# CanBus.net
KiCad netlist of a schematic drawn in EAGLE
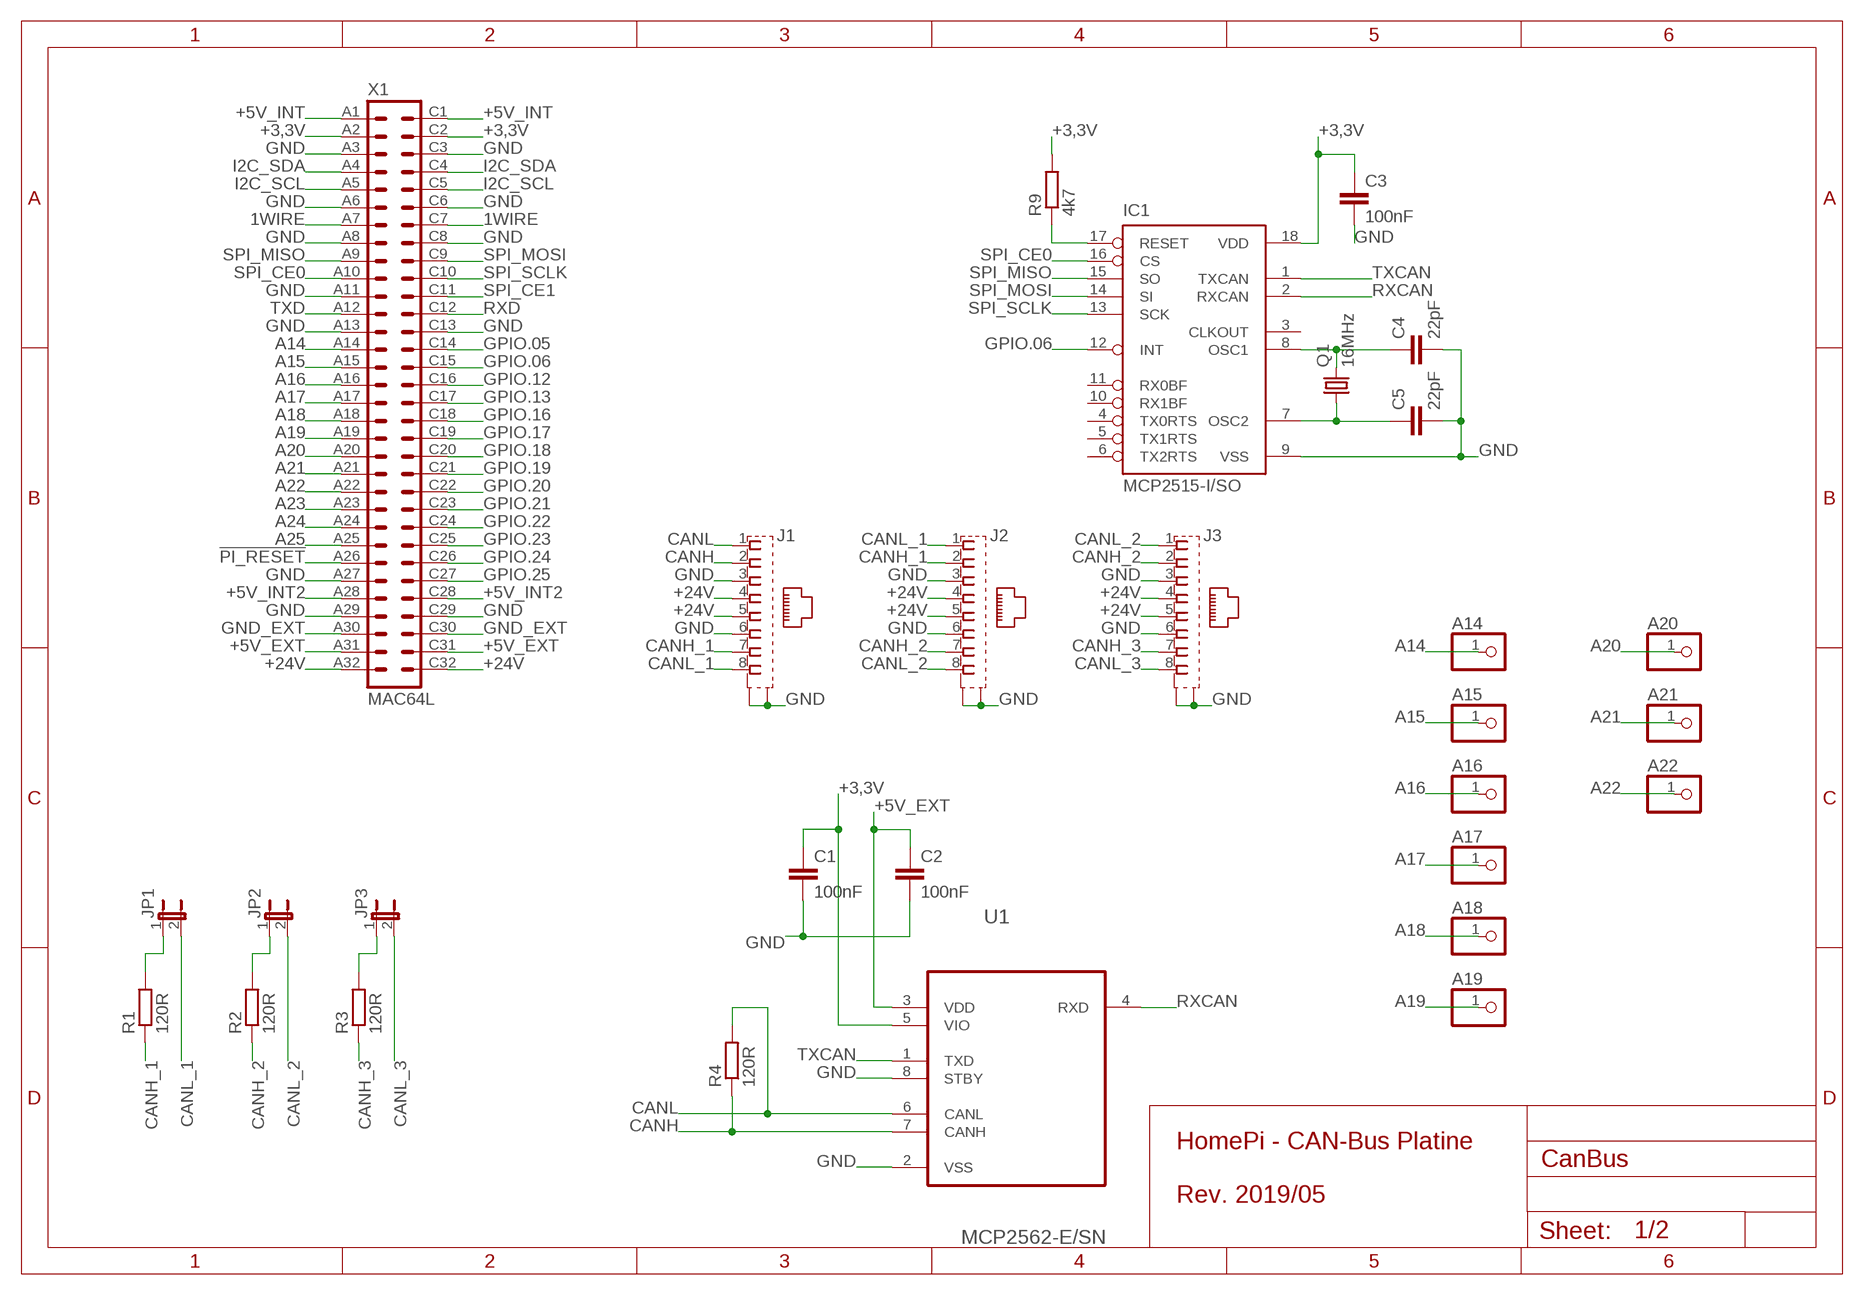
[diagram p0: schematic, sheet 1]
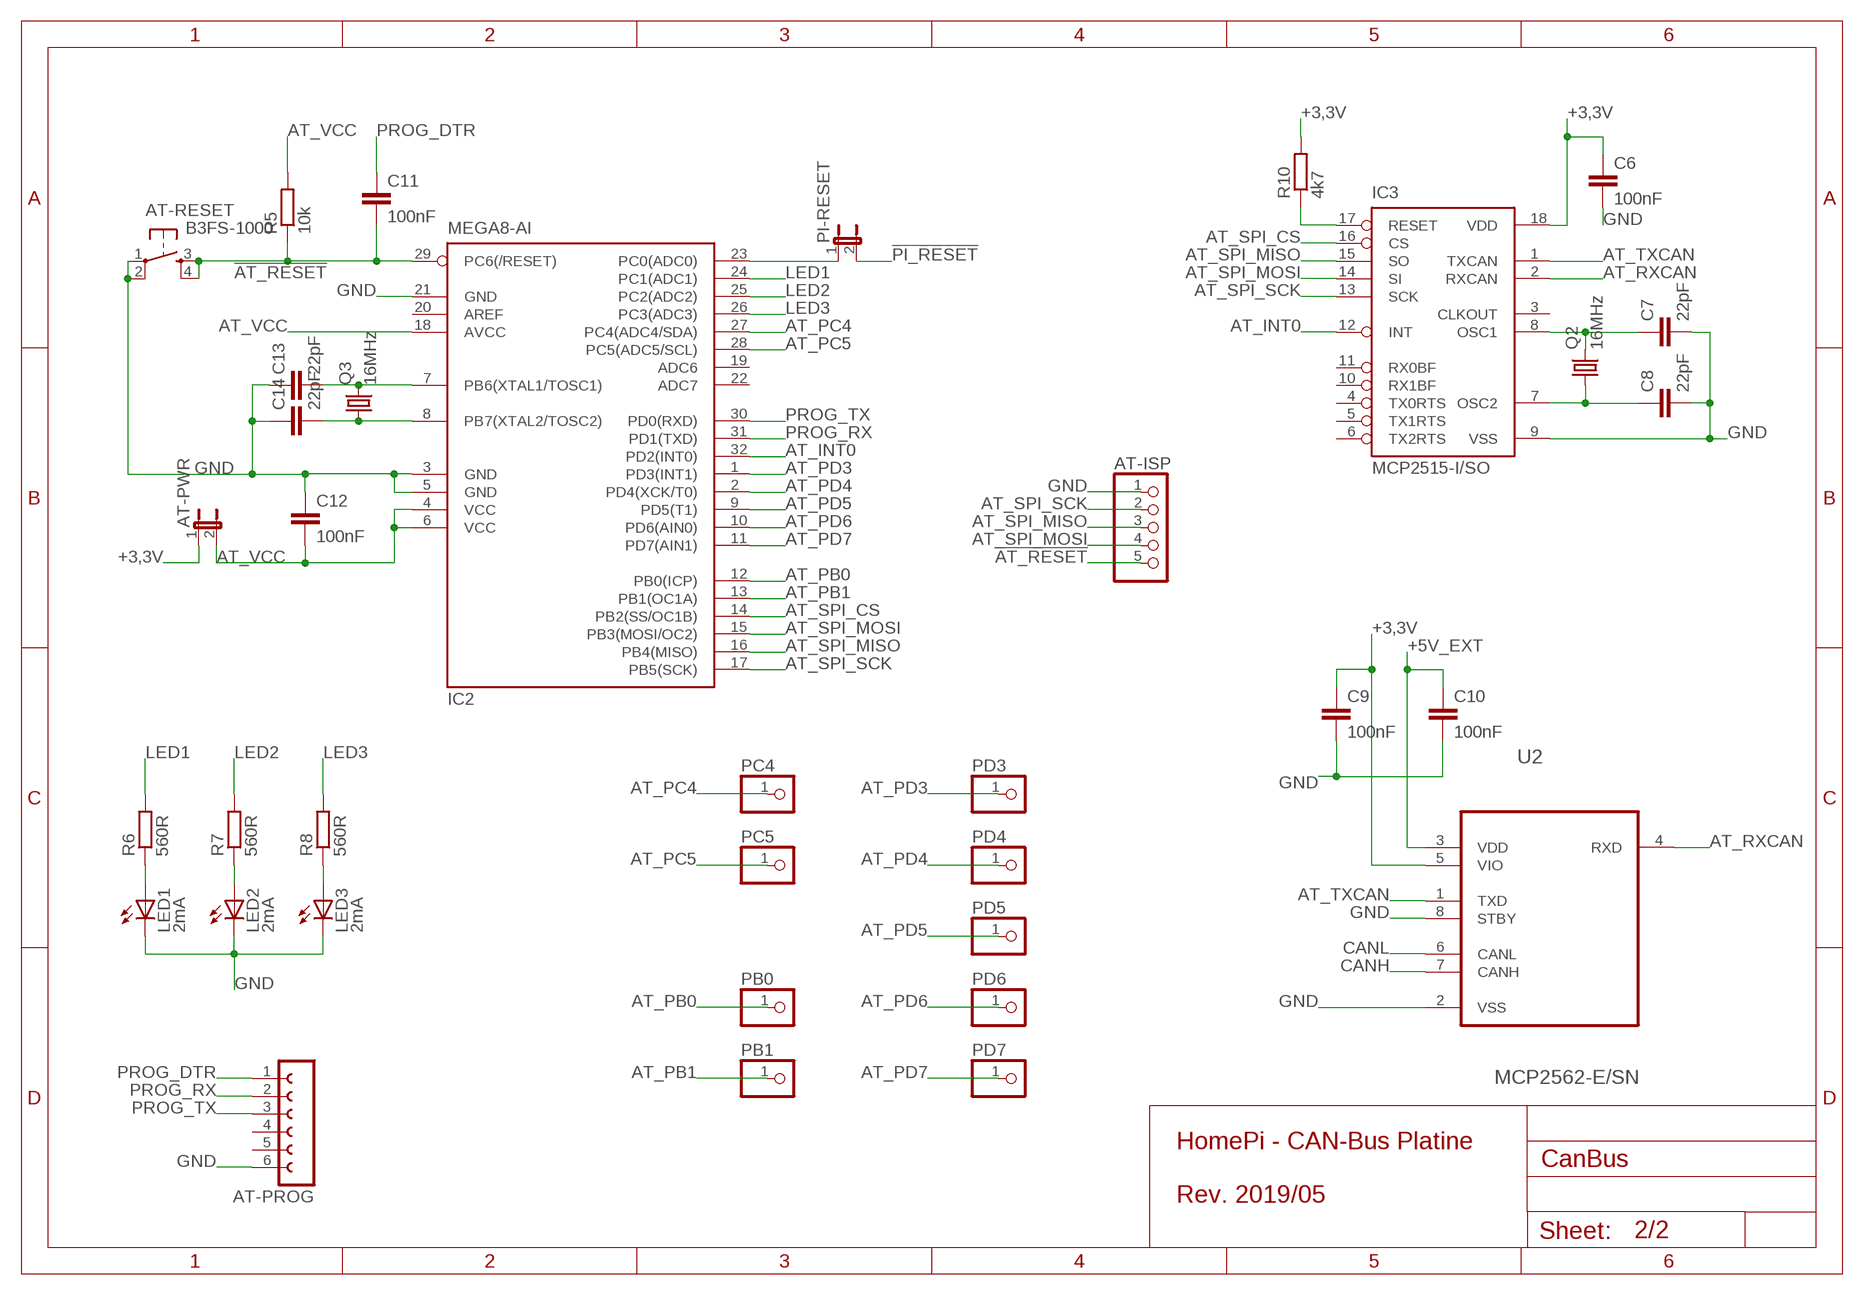
[diagram p1: schematic, sheet 2]

(export (version "E")
  (design (tool "Eeschema 10.0.6"))
  (components
    (comp (ref "AT-ISP")
      (value "PINHD-1X5")
      (footprint "eagle-import:1X05")
      (libsource (lib "eagle-import") (part "PINHD-1X5"))
    )
    (comp (ref "AT-PROG")
      (value "FE06W")
      (footprint "eagle-import:FE06W")
      (libsource (lib "eagle-import") (part "FE06W"))
    )
    (comp (ref "AT-PWR")
      (value "JP1E")
      (footprint "eagle-import:JP1")
      (libsource (lib "eagle-import") (part "JP1E"))
    )
    (comp (ref "AT-RESET")
      (value "B3FS-1000")
      (footprint "eagle-import:B3FS-1000")
      (libsource (lib "eagle-import") (part "B3FS-1000"))
    )
    (comp (ref "C6")
      (value "100nF")
      (footprint "eagle-import:C1206")
      (libsource (lib "eagle-import") (part "C-EUC1206"))
    )
    (comp (ref "C7")
      (value "22pF")
      (footprint "eagle-import:C1206")
      (libsource (lib "eagle-import") (part "C-EUC1206"))
    )
    (comp (ref "C8")
      (value "22pF")
      (footprint "eagle-import:C1206")
      (libsource (lib "eagle-import") (part "C-EUC1206"))
    )
    (comp (ref "C9")
      (value "100nF")
      (footprint "eagle-import:C1206")
      (libsource (lib "eagle-import") (part "C-EUC1206"))
    )
    (comp (ref "C10")
      (value "100nF")
      (footprint "eagle-import:C1206")
      (libsource (lib "eagle-import") (part "C-EUC1206"))
    )
    (comp (ref "C11")
      (value "100nF")
      (footprint "eagle-import:C1206")
      (libsource (lib "eagle-import") (part "C-EUC1206"))
    )
    (comp (ref "C12")
      (value "100nF")
      (footprint "eagle-import:C1206")
      (libsource (lib "eagle-import") (part "C-EUC1206"))
    )
    (comp (ref "C13")
      (value "22pF")
      (footprint "eagle-import:C1206")
      (libsource (lib "eagle-import") (part "C-EUC1206"))
    )
    (comp (ref "C14")
      (value "22pF")
      (footprint "eagle-import:C1206")
      (libsource (lib "eagle-import") (part "C-EUC1206"))
    )
    (comp (ref "IC2")
      (value "MEGA8-AI")
      (footprint "eagle-import:TQFP32-08")
      (fields (field (name "MPN") "ATMEGA8-16AU"))
      (libsource (lib "eagle-import") (part "MEGA8-AI"))
    )
    (comp (ref "IC3")
      (value "MCP2515-I/SO")
      (footprint "eagle-import:SO18L")
      (libsource (lib "eagle-import") (part "MCP2515-I/SO"))
    )
    (comp (ref "LED1")
      (value "2mA")
      (footprint "eagle-import:LED3MM")
      (libsource (lib "eagle-import") (part "LED3MM"))
    )
    (comp (ref "LED2")
      (value "2mA")
      (footprint "eagle-import:LED3MM")
      (libsource (lib "eagle-import") (part "LED3MM"))
    )
    (comp (ref "LED3")
      (value "2mA")
      (footprint "eagle-import:LED3MM")
      (libsource (lib "eagle-import") (part "LED3MM"))
    )
    (comp (ref "PB0")
      (value "PINHD-1X1")
      (footprint "eagle-import:1X01")
      (libsource (lib "eagle-import") (part "PINHD-1X1"))
    )
    (comp (ref "PB1")
      (value "PINHD-1X1")
      (footprint "eagle-import:1X01")
      (libsource (lib "eagle-import") (part "PINHD-1X1"))
    )
    (comp (ref "PC4")
      (value "PINHD-1X1")
      (footprint "eagle-import:1X01")
      (libsource (lib "eagle-import") (part "PINHD-1X1"))
    )
    (comp (ref "PC5")
      (value "PINHD-1X1")
      (footprint "eagle-import:1X01")
      (libsource (lib "eagle-import") (part "PINHD-1X1"))
    )
    (comp (ref "PD3")
      (value "PINHD-1X1")
      (footprint "eagle-import:1X01")
      (libsource (lib "eagle-import") (part "PINHD-1X1"))
    )
    (comp (ref "PD4")
      (value "PINHD-1X1")
      (footprint "eagle-import:1X01")
      (libsource (lib "eagle-import") (part "PINHD-1X1"))
    )
    (comp (ref "PD5")
      (value "PINHD-1X1")
      (footprint "eagle-import:1X01")
      (libsource (lib "eagle-import") (part "PINHD-1X1"))
    )
    (comp (ref "PD6")
      (value "PINHD-1X1")
      (footprint "eagle-import:1X01")
      (libsource (lib "eagle-import") (part "PINHD-1X1"))
    )
    (comp (ref "PD7")
      (value "PINHD-1X1")
      (footprint "eagle-import:1X01")
      (libsource (lib "eagle-import") (part "PINHD-1X1"))
    )
    (comp (ref "PI-RESET")
      (value "JP1E")
      (footprint "eagle-import:JP1")
      (libsource (lib "eagle-import") (part "JP1E"))
    )
    (comp (ref "Q2")
      (value "16MHz")
      (footprint "eagle-import:HC49UP")
      (libsource (lib "eagle-import") (part "CRYSTALHC49UP"))
    )
    (comp (ref "Q3")
      (value "16MHz")
      (footprint "eagle-import:HC49UP")
      (libsource (lib "eagle-import") (part "CRYSTALHC49UP"))
    )
    (comp (ref "R5")
      (value "10k")
      (footprint "eagle-import:R1206")
      (libsource (lib "eagle-import") (part "R-EU_R1206"))
    )
    (comp (ref "R6")
      (value "560R")
      (footprint "eagle-import:R1206")
      (libsource (lib "eagle-import") (part "R-EU_R1206"))
    )
    (comp (ref "R7")
      (value "560R")
      (footprint "eagle-import:R1206")
      (libsource (lib "eagle-import") (part "R-EU_R1206"))
    )
    (comp (ref "R8")
      (value "560R")
      (footprint "eagle-import:R1206")
      (libsource (lib "eagle-import") (part "R-EU_R1206"))
    )
    (comp (ref "R10")
      (value "4k7")
      (footprint "eagle-import:R1206")
      (libsource (lib "eagle-import") (part "R-EU_R1206"))
    )
    (comp (ref "U2")
      (value "MCP2562-E/SN")
      (footprint "eagle-import:SO08")
      (libsource (lib "eagle-import") (part "MCP2562-E/SN"))
    )
    (comp (ref "A14")
      (value "PINHD-1X1")
      (footprint "eagle-import:1X01")
      (libsource (lib "eagle-import") (part "PINHD-1X1"))
    )
    (comp (ref "A15")
      (value "PINHD-1X1")
      (footprint "eagle-import:1X01")
      (libsource (lib "eagle-import") (part "PINHD-1X1"))
    )
    (comp (ref "A16")
      (value "PINHD-1X1")
      (footprint "eagle-import:1X01")
      (libsource (lib "eagle-import") (part "PINHD-1X1"))
    )
    (comp (ref "A17")
      (value "PINHD-1X1")
      (footprint "eagle-import:1X01")
      (libsource (lib "eagle-import") (part "PINHD-1X1"))
    )
    (comp (ref "A18")
      (value "PINHD-1X1")
      (footprint "eagle-import:1X01")
      (libsource (lib "eagle-import") (part "PINHD-1X1"))
    )
    (comp (ref "A19")
      (value "PINHD-1X1")
      (footprint "eagle-import:1X01")
      (libsource (lib "eagle-import") (part "PINHD-1X1"))
    )
    (comp (ref "A20")
      (value "PINHD-1X1")
      (footprint "eagle-import:1X01")
      (libsource (lib "eagle-import") (part "PINHD-1X1"))
    )
    (comp (ref "A21")
      (value "PINHD-1X1")
      (footprint "eagle-import:1X01")
      (libsource (lib "eagle-import") (part "PINHD-1X1"))
    )
    (comp (ref "A22")
      (value "PINHD-1X1")
      (footprint "eagle-import:1X01")
      (libsource (lib "eagle-import") (part "PINHD-1X1"))
    )
    (comp (ref "C1")
      (value "100nF")
      (footprint "eagle-import:C1206")
      (libsource (lib "eagle-import") (part "C-EUC1206"))
    )
    (comp (ref "C2")
      (value "100nF")
      (footprint "eagle-import:C1206")
      (libsource (lib "eagle-import") (part "C-EUC1206"))
    )
    (comp (ref "C3")
      (value "100nF")
      (footprint "eagle-import:C1206")
      (libsource (lib "eagle-import") (part "C-EUC1206"))
    )
    (comp (ref "C4")
      (value "22pF")
      (footprint "eagle-import:C1206")
      (libsource (lib "eagle-import") (part "C-EUC1206"))
    )
    (comp (ref "C5")
      (value "22pF")
      (footprint "eagle-import:C1206")
      (libsource (lib "eagle-import") (part "C-EUC1206"))
    )
    (comp (ref "IC1")
      (value "MCP2515-I/SO")
      (footprint "eagle-import:SO18L")
      (libsource (lib "eagle-import") (part "MCP2515-I/SO"))
    )
    (comp (ref "J1")
      (value "555141-1")
      (footprint "eagle-import:MEBP_8-8G")
      (libsource (lib "eagle-import") (part "555141-1"))
    )
    (comp (ref "J2")
      (value "555141-1")
      (footprint "eagle-import:MEBP_8-8G")
      (libsource (lib "eagle-import") (part "555141-1"))
    )
    (comp (ref "J3")
      (value "555141-1")
      (footprint "eagle-import:MEBP_8-8G")
      (libsource (lib "eagle-import") (part "555141-1"))
    )
    (comp (ref "JP1")
      (value "JP1E")
      (footprint "eagle-import:JP1")
      (libsource (lib "eagle-import") (part "JP1E"))
    )
    (comp (ref "JP2")
      (value "JP1E")
      (footprint "eagle-import:JP1")
      (libsource (lib "eagle-import") (part "JP1E"))
    )
    (comp (ref "JP3")
      (value "JP1E")
      (footprint "eagle-import:JP1")
      (libsource (lib "eagle-import") (part "JP1E"))
    )
    (comp (ref "Q1")
      (value "16MHz")
      (footprint "eagle-import:HC49UP")
      (libsource (lib "eagle-import") (part "CRYSTALHC49UP"))
    )
    (comp (ref "R1")
      (value "120R")
      (footprint "eagle-import:R1206")
      (libsource (lib "eagle-import") (part "R-EU_R1206"))
    )
    (comp (ref "R2")
      (value "120R")
      (footprint "eagle-import:R1206")
      (libsource (lib "eagle-import") (part "R-EU_R1206"))
    )
    (comp (ref "R3")
      (value "120R")
      (footprint "eagle-import:R1206")
      (libsource (lib "eagle-import") (part "R-EU_R1206"))
    )
    (comp (ref "R4")
      (value "120R")
      (footprint "eagle-import:R1206")
      (libsource (lib "eagle-import") (part "R-EU_R1206"))
    )
    (comp (ref "R9")
      (value "4k7")
      (footprint "eagle-import:R1206")
      (libsource (lib "eagle-import") (part "R-EU_R1206"))
    )
    (comp (ref "U1")
      (value "MCP2562-E/SN")
      (footprint "eagle-import:SO08")
      (libsource (lib "eagle-import") (part "MCP2562-E/SN"))
    )
    (comp (ref "X1")
      (value "MAC64L")
      (footprint "eagle-import:MAC64L")
      (libsource (lib "eagle-import") (part "MAC64L"))
    )
  )
  (nets
    (net (code "1") (name "+3,3V") (class "Default")
      (node (ref "AT-PWR") (pin "1") (pinfunction "1_1") (pintype "passive"))
      (node (ref "C1") (pin "1") (pinfunction "1_1") (pintype "passive"))
      (node (ref "C3") (pin "1") (pinfunction "1_1") (pintype "passive"))
      (node (ref "C6") (pin "1") (pinfunction "1_1") (pintype "passive"))
      (node (ref "C9") (pin "1") (pinfunction "1_1") (pintype "passive"))
      (node (ref "IC1") (pin "18") (pinfunction "VDD_18") (pintype "power_in"))
      (node (ref "IC3") (pin "18") (pinfunction "VDD_18") (pintype "power_in"))
      (node (ref "R10") (pin "2") (pinfunction "2_2") (pintype "passive"))
      (node (ref "R9") (pin "2") (pinfunction "2_2") (pintype "passive"))
      (node (ref "U1") (pin "5") (pinfunction "VIO_5") (pintype "power_in"))
      (node (ref "U2") (pin "5") (pinfunction "VIO_5") (pintype "power_in"))
      (node (ref "X1") (pin "A2") (pinfunction "A2_A2") (pintype "passive"))
      (node (ref "X1") (pin "C2") (pinfunction "C2_C2") (pintype "passive"))
    )
    (net (code "2") (name "+5V_EXT") (class "Default")
      (node (ref "C10") (pin "1") (pinfunction "1_1") (pintype "passive"))
      (node (ref "C2") (pin "1") (pinfunction "1_1") (pintype "passive"))
      (node (ref "U1") (pin "3") (pinfunction "VDD_3") (pintype "power_in"))
      (node (ref "U2") (pin "3") (pinfunction "VDD_3") (pintype "power_in"))
      (node (ref "X1") (pin "A31") (pinfunction "A31_A31") (pintype "passive"))
      (node (ref "X1") (pin "C31") (pinfunction "C31_C31") (pintype "passive"))
    )
    (net (code "3") (name "+5V_INT") (class "Default")
      (node (ref "X1") (pin "A1") (pinfunction "A1_A1") (pintype "passive"))
      (node (ref "X1") (pin "C1") (pinfunction "C1_C1") (pintype "passive"))
    )
    (net (code "4") (name "+5V_INT2") (class "Default")
      (node (ref "X1") (pin "A28") (pinfunction "A28_A28") (pintype "passive"))
      (node (ref "X1") (pin "C28") (pinfunction "C28_C28") (pintype "passive"))
    )
    (net (code "5") (name "+24V") (class "Default")
      (node (ref "J1") (pin "4") (pinfunction "4_4") (pintype "passive"))
      (node (ref "J1") (pin "5") (pinfunction "5_5") (pintype "passive"))
      (node (ref "J2") (pin "4") (pinfunction "4_4") (pintype "passive"))
      (node (ref "J2") (pin "5") (pinfunction "5_5") (pintype "passive"))
      (node (ref "J3") (pin "4") (pinfunction "4_4") (pintype "passive"))
      (node (ref "J3") (pin "5") (pinfunction "5_5") (pintype "passive"))
      (node (ref "X1") (pin "A32") (pinfunction "A32_A32") (pintype "passive"))
      (node (ref "X1") (pin "C32") (pinfunction "C32_C32") (pintype "passive"))
    )
    (net (code "6") (name "1WIRE") (class "Default")
      (node (ref "X1") (pin "A7") (pinfunction "A7_A7") (pintype "passive"))
      (node (ref "X1") (pin "C7") (pinfunction "C7_C7") (pintype "passive"))
    )
    (net (code "7") (name "A14") (class "Default")
      (node (ref "A14") (pin "1") (pinfunction "1_1") (pintype "passive"))
      (node (ref "X1") (pin "A14") (pinfunction "A14_A14") (pintype "passive"))
    )
    (net (code "8") (name "A15") (class "Default")
      (node (ref "A15") (pin "1") (pinfunction "1_1") (pintype "passive"))
      (node (ref "X1") (pin "A15") (pinfunction "A15_A15") (pintype "passive"))
    )
    (net (code "9") (name "A16") (class "Default")
      (node (ref "A16") (pin "1") (pinfunction "1_1") (pintype "passive"))
      (node (ref "X1") (pin "A16") (pinfunction "A16_A16") (pintype "passive"))
    )
    (net (code "10") (name "A17") (class "Default")
      (node (ref "A17") (pin "1") (pinfunction "1_1") (pintype "passive"))
      (node (ref "X1") (pin "A17") (pinfunction "A17_A17") (pintype "passive"))
    )
    (net (code "11") (name "A18") (class "Default")
      (node (ref "A18") (pin "1") (pinfunction "1_1") (pintype "passive"))
      (node (ref "X1") (pin "A18") (pinfunction "A18_A18") (pintype "passive"))
    )
    (net (code "12") (name "A19") (class "Default")
      (node (ref "A19") (pin "1") (pinfunction "1_1") (pintype "passive"))
      (node (ref "X1") (pin "A19") (pinfunction "A19_A19") (pintype "passive"))
    )
    (net (code "13") (name "A20") (class "Default")
      (node (ref "A20") (pin "1") (pinfunction "1_1") (pintype "passive"))
      (node (ref "X1") (pin "A20") (pinfunction "A20_A20") (pintype "passive"))
    )
    (net (code "14") (name "A21") (class "Default")
      (node (ref "A21") (pin "1") (pinfunction "1_1") (pintype "passive"))
      (node (ref "X1") (pin "A21") (pinfunction "A21_A21") (pintype "passive"))
    )
    (net (code "15") (name "A22") (class "Default")
      (node (ref "A22") (pin "1") (pinfunction "1_1") (pintype "passive"))
      (node (ref "X1") (pin "A22") (pinfunction "A22_A22") (pintype "passive"))
    )
    (net (code "16") (name "A23") (class "Default")
      (node (ref "X1") (pin "A23") (pinfunction "A23_A23") (pintype "passive"))
    )
    (net (code "17") (name "A24") (class "Default")
      (node (ref "X1") (pin "A24") (pinfunction "A24_A24") (pintype "passive"))
    )
    (net (code "18") (name "A25") (class "Default")
      (node (ref "X1") (pin "A25") (pinfunction "A25_A25") (pintype "passive"))
    )
    (net (code "19") (name "AT_INT0") (class "Default")
      (node (ref "IC2") (pin "32") (pinfunction "PD2(INT0)_32") (pintype "bidirectional"))
      (node (ref "IC3") (pin "12") (pinfunction "INT_12") (pintype "output"))
    )
    (net (code "20") (name "AT_PB0") (class "Default")
      (node (ref "IC2") (pin "12") (pinfunction "PB0(ICP)_12") (pintype "bidirectional"))
      (node (ref "PB0") (pin "1") (pinfunction "1_1") (pintype "passive"))
    )
    (net (code "21") (name "AT_PB1") (class "Default")
      (node (ref "IC2") (pin "13") (pinfunction "PB1(OC1A)_13") (pintype "bidirectional"))
      (node (ref "PB1") (pin "1") (pinfunction "1_1") (pintype "passive"))
    )
    (net (code "22") (name "AT_PC4") (class "Default")
      (node (ref "IC2") (pin "27") (pinfunction "PC4(ADC4/SDA)_27") (pintype "bidirectional"))
      (node (ref "PC4") (pin "1") (pinfunction "1_1") (pintype "passive"))
    )
    (net (code "23") (name "AT_PC5") (class "Default")
      (node (ref "IC2") (pin "28") (pinfunction "PC5(ADC5/SCL)_28") (pintype "bidirectional"))
      (node (ref "PC5") (pin "1") (pinfunction "1_1") (pintype "passive"))
    )
    (net (code "24") (name "AT_PD3") (class "Default")
      (node (ref "IC2") (pin "1") (pinfunction "PD3(INT1)_1") (pintype "bidirectional"))
      (node (ref "PD3") (pin "1") (pinfunction "1_1") (pintype "passive"))
    )
    (net (code "25") (name "AT_PD4") (class "Default")
      (node (ref "IC2") (pin "2") (pinfunction "PD4(XCK/T0)_2") (pintype "bidirectional"))
      (node (ref "PD4") (pin "1") (pinfunction "1_1") (pintype "passive"))
    )
    (net (code "26") (name "AT_PD5") (class "Default")
      (node (ref "IC2") (pin "9") (pinfunction "PD5(T1)_9") (pintype "bidirectional"))
      (node (ref "PD5") (pin "1") (pinfunction "1_1") (pintype "passive"))
    )
    (net (code "27") (name "AT_PD6") (class "Default")
      (node (ref "IC2") (pin "10") (pinfunction "PD6(AIN0)_10") (pintype "bidirectional"))
      (node (ref "PD6") (pin "1") (pinfunction "1_1") (pintype "passive"))
    )
    (net (code "28") (name "AT_PD7") (class "Default")
      (node (ref "IC2") (pin "11") (pinfunction "PD7(AIN1)_11") (pintype "bidirectional"))
      (node (ref "PD7") (pin "1") (pinfunction "1_1") (pintype "passive"))
    )
    (net (code "29") (name "AT_RXCAN") (class "Default")
      (node (ref "IC3") (pin "2") (pinfunction "RXCAN_2") (pintype "input"))
      (node (ref "U2") (pin "4") (pinfunction "RXD_4") (pintype "output"))
    )
    (net (code "30") (name "AT_SPI_CS") (class "Default")
      (node (ref "IC2") (pin "14") (pinfunction "PB2(SS/OC1B)_14") (pintype "bidirectional"))
      (node (ref "IC3") (pin "16") (pinfunction "CS_16") (pintype "input"))
    )
    (net (code "31") (name "AT_SPI_MISO") (class "Default")
      (node (ref "AT-ISP") (pin "3") (pinfunction "3_3") (pintype "passive"))
      (node (ref "IC2") (pin "16") (pinfunction "PB4(MISO)_16") (pintype "bidirectional"))
      (node (ref "IC3") (pin "15") (pinfunction "SO_15") (pintype "output"))
    )
    (net (code "32") (name "AT_SPI_MOSI") (class "Default")
      (node (ref "AT-ISP") (pin "4") (pinfunction "4_4") (pintype "passive"))
      (node (ref "IC2") (pin "15") (pinfunction "PB3(MOSI/OC2)_15") (pintype "bidirectional"))
      (node (ref "IC3") (pin "14") (pinfunction "SI_14") (pintype "input"))
    )
    (net (code "33") (name "AT_SPI_SCK") (class "Default")
      (node (ref "AT-ISP") (pin "2") (pinfunction "2_2") (pintype "passive"))
      (node (ref "IC2") (pin "17") (pinfunction "PB5(SCK)_17") (pintype "bidirectional"))
      (node (ref "IC3") (pin "13") (pinfunction "SCK_13") (pintype "input"))
    )
    (net (code "34") (name "AT_TXCAN") (class "Default")
      (node (ref "IC3") (pin "1") (pinfunction "TXCAN_1") (pintype "output"))
      (node (ref "U2") (pin "1") (pinfunction "TXD_1") (pintype "input"))
    )
    (net (code "35") (name "AT_VCC") (class "Default")
      (node (ref "AT-PWR") (pin "2") (pinfunction "2_2") (pintype "passive"))
      (node (ref "C12") (pin "2") (pinfunction "2_2") (pintype "passive"))
      (node (ref "IC2") (pin "18") (pinfunction "AVCC_18") (pintype "power_in"))
      (node (ref "IC2") (pin "4") (pinfunction "VCC_4") (pintype "power_in"))
      (node (ref "IC2") (pin "6") (pinfunction "VCC_6") (pintype "power_in"))
      (node (ref "R5") (pin "2") (pinfunction "2_2") (pintype "passive"))
    )
    (net (code "36") (name "CANH") (class "Default")
      (node (ref "J1") (pin "2") (pinfunction "2_2") (pintype "passive"))
      (node (ref "R4") (pin "1") (pinfunction "1_1") (pintype "passive"))
      (node (ref "U1") (pin "7") (pinfunction "CANH_7") (pintype "bidirectional"))
      (node (ref "U2") (pin "7") (pinfunction "CANH_7") (pintype "bidirectional"))
    )
    (net (code "37") (name "CANH_1") (class "Default")
      (node (ref "J1") (pin "7") (pinfunction "7_7") (pintype "passive"))
      (node (ref "J2") (pin "2") (pinfunction "2_2") (pintype "passive"))
      (node (ref "R1") (pin "1") (pinfunction "1_1") (pintype "passive"))
    )
    (net (code "38") (name "CANH_2") (class "Default")
      (node (ref "J2") (pin "7") (pinfunction "7_7") (pintype "passive"))
      (node (ref "J3") (pin "2") (pinfunction "2_2") (pintype "passive"))
      (node (ref "R2") (pin "1") (pinfunction "1_1") (pintype "passive"))
    )
    (net (code "39") (name "CANH_3") (class "Default")
      (node (ref "J3") (pin "7") (pinfunction "7_7") (pintype "passive"))
      (node (ref "R3") (pin "1") (pinfunction "1_1") (pintype "passive"))
    )
    (net (code "40") (name "CANL") (class "Default")
      (node (ref "J1") (pin "1") (pinfunction "1_1") (pintype "passive"))
      (node (ref "R4") (pin "2") (pinfunction "2_2") (pintype "passive"))
      (node (ref "U1") (pin "6") (pinfunction "CANL_6") (pintype "bidirectional"))
      (node (ref "U2") (pin "6") (pinfunction "CANL_6") (pintype "bidirectional"))
    )
    (net (code "41") (name "CANL_1") (class "Default")
      (node (ref "J1") (pin "8") (pinfunction "8_8") (pintype "passive"))
      (node (ref "J2") (pin "1") (pinfunction "1_1") (pintype "passive"))
      (node (ref "JP1") (pin "2") (pinfunction "2_2") (pintype "passive"))
    )
    (net (code "42") (name "CANL_2") (class "Default")
      (node (ref "J2") (pin "8") (pinfunction "8_8") (pintype "passive"))
      (node (ref "J3") (pin "1") (pinfunction "1_1") (pintype "passive"))
      (node (ref "JP2") (pin "2") (pinfunction "2_2") (pintype "passive"))
    )
    (net (code "43") (name "CANL_3") (class "Default")
      (node (ref "J3") (pin "8") (pinfunction "8_8") (pintype "passive"))
      (node (ref "JP3") (pin "2") (pinfunction "2_2") (pintype "passive"))
    )
    (net (code "44") (name "GND") (class "Default")
      (node (ref "AT-ISP") (pin "1") (pinfunction "1_1") (pintype "passive"))
      (node (ref "AT-PROG") (pin "6") (pinfunction "6_6") (pintype "passive"))
      (node (ref "AT-RESET") (pin "1") (pinfunction "P_1") (pintype "passive"))
      (node (ref "AT-RESET") (pin "2") (pinfunction "P1_2") (pintype "passive"))
      (node (ref "C1") (pin "2") (pinfunction "2_2") (pintype "passive"))
      (node (ref "C10") (pin "2") (pinfunction "2_2") (pintype "passive"))
      (node (ref "C12") (pin "1") (pinfunction "1_1") (pintype "passive"))
      (node (ref "C13") (pin "1") (pinfunction "1_1") (pintype "passive"))
      (node (ref "C14") (pin "1") (pinfunction "1_1") (pintype "passive"))
      (node (ref "C2") (pin "2") (pinfunction "2_2") (pintype "passive"))
      (node (ref "C3") (pin "2") (pinfunction "2_2") (pintype "passive"))
      (node (ref "C4") (pin "2") (pinfunction "2_2") (pintype "passive"))
      (node (ref "C5") (pin "2") (pinfunction "2_2") (pintype "passive"))
      (node (ref "C6") (pin "2") (pinfunction "2_2") (pintype "passive"))
      (node (ref "C7") (pin "2") (pinfunction "2_2") (pintype "passive"))
      (node (ref "C8") (pin "2") (pinfunction "2_2") (pintype "passive"))
      (node (ref "C9") (pin "2") (pinfunction "2_2") (pintype "passive"))
      (node (ref "IC1") (pin "9") (pinfunction "VSS_9") (pintype "power_in"))
      (node (ref "IC2") (pin "21") (pinfunction "GND_21") (pintype "power_in"))
      (node (ref "IC2") (pin "3") (pinfunction "GND_3") (pintype "power_in"))
      (node (ref "IC2") (pin "5") (pinfunction "GND_5") (pintype "power_in"))
      (node (ref "IC3") (pin "9") (pinfunction "VSS_9") (pintype "power_in"))
      (node (ref "J1") (pin "3") (pinfunction "3_3") (pintype "passive"))
      (node (ref "J1") (pin "6") (pinfunction "6_6") (pintype "passive"))
      (node (ref "J1") (pin "G1") (pinfunction "S1_G1") (pintype "passive"))
      (node (ref "J1") (pin "G2") (pinfunction "S2_G2") (pintype "passive"))
      (node (ref "J2") (pin "3") (pinfunction "3_3") (pintype "passive"))
      (node (ref "J2") (pin "6") (pinfunction "6_6") (pintype "passive"))
      (node (ref "J2") (pin "G1") (pinfunction "S1_G1") (pintype "passive"))
      (node (ref "J2") (pin "G2") (pinfunction "S2_G2") (pintype "passive"))
      (node (ref "J3") (pin "3") (pinfunction "3_3") (pintype "passive"))
      (node (ref "J3") (pin "6") (pinfunction "6_6") (pintype "passive"))
      (node (ref "J3") (pin "G1") (pinfunction "S1_G1") (pintype "passive"))
      (node (ref "J3") (pin "G2") (pinfunction "S2_G2") (pintype "passive"))
      (node (ref "LED1") (pin "K") (pinfunction "C_K") (pintype "passive"))
      (node (ref "LED2") (pin "K") (pinfunction "C_K") (pintype "passive"))
      (node (ref "LED3") (pin "K") (pinfunction "C_K") (pintype "passive"))
      (node (ref "U1") (pin "2") (pinfunction "VSS_2") (pintype "power_in"))
      (node (ref "U1") (pin "8") (pinfunction "STBY_8") (pintype "input"))
      (node (ref "U2") (pin "2") (pinfunction "VSS_2") (pintype "power_in"))
      (node (ref "U2") (pin "8") (pinfunction "STBY_8") (pintype "input"))
      (node (ref "X1") (pin "A11") (pinfunction "A11_A11") (pintype "passive"))
      (node (ref "X1") (pin "A13") (pinfunction "A13_A13") (pintype "passive"))
      (node (ref "X1") (pin "A27") (pinfunction "A27_A27") (pintype "passive"))
      (node (ref "X1") (pin "A29") (pinfunction "A29_A29") (pintype "passive"))
      (node (ref "X1") (pin "A3") (pinfunction "A3_A3") (pintype "passive"))
      (node (ref "X1") (pin "A6") (pinfunction "A6_A6") (pintype "passive"))
      (node (ref "X1") (pin "A8") (pinfunction "A8_A8") (pintype "passive"))
      (node (ref "X1") (pin "C13") (pinfunction "C13_C13") (pintype "passive"))
      (node (ref "X1") (pin "C29") (pinfunction "C29_C29") (pintype "passive"))
      (node (ref "X1") (pin "C3") (pinfunction "C3_C3") (pintype "passive"))
      (node (ref "X1") (pin "C6") (pinfunction "C6_C6") (pintype "passive"))
      (node (ref "X1") (pin "C8") (pinfunction "C8_C8") (pintype "passive"))
    )
    (net (code "45") (name "GND_EXT") (class "Default")
      (node (ref "X1") (pin "A30") (pinfunction "A30_A30") (pintype "passive"))
      (node (ref "X1") (pin "C30") (pinfunction "C30_C30") (pintype "passive"))
    )
    (net (code "46") (name "GPIO.05") (class "Default")
      (node (ref "X1") (pin "C14") (pinfunction "C14_C14") (pintype "passive"))
    )
    (net (code "47") (name "GPIO.06") (class "Default")
      (node (ref "IC1") (pin "12") (pinfunction "INT_12") (pintype "output"))
      (node (ref "X1") (pin "C15") (pinfunction "C15_C15") (pintype "passive"))
    )
    (net (code "48") (name "GPIO.12") (class "Default")
      (node (ref "X1") (pin "C16") (pinfunction "C16_C16") (pintype "passive"))
    )
    (net (code "49") (name "GPIO.13") (class "Default")
      (node (ref "X1") (pin "C17") (pinfunction "C17_C17") (pintype "passive"))
    )
    (net (code "50") (name "GPIO.16") (class "Default")
      (node (ref "X1") (pin "C18") (pinfunction "C18_C18") (pintype "passive"))
    )
    (net (code "51") (name "GPIO.17") (class "Default")
      (node (ref "X1") (pin "C19") (pinfunction "C19_C19") (pintype "passive"))
    )
    (net (code "52") (name "GPIO.18") (class "Default")
      (node (ref "X1") (pin "C20") (pinfunction "C20_C20") (pintype "passive"))
    )
    (net (code "53") (name "GPIO.19") (class "Default")
      (node (ref "X1") (pin "C21") (pinfunction "C21_C21") (pintype "passive"))
    )
    (net (code "54") (name "GPIO.20") (class "Default")
      (node (ref "X1") (pin "C22") (pinfunction "C22_C22") (pintype "passive"))
    )
    (net (code "55") (name "GPIO.21") (class "Default")
      (node (ref "X1") (pin "C23") (pinfunction "C23_C23") (pintype "passive"))
    )
    (net (code "56") (name "GPIO.22") (class "Default")
      (node (ref "X1") (pin "C24") (pinfunction "C24_C24") (pintype "passive"))
    )
    (net (code "57") (name "GPIO.23") (class "Default")
      (node (ref "X1") (pin "C25") (pinfunction "C25_C25") (pintype "passive"))
    )
    (net (code "58") (name "GPIO.24") (class "Default")
      (node (ref "X1") (pin "C26") (pinfunction "C26_C26") (pintype "passive"))
    )
    (net (code "59") (name "GPIO.25") (class "Default")
      (node (ref "X1") (pin "C27") (pinfunction "C27_C27") (pintype "passive"))
    )
    (net (code "60") (name "I2C_SCL") (class "Default")
      (node (ref "X1") (pin "A5") (pinfunction "A5_A5") (pintype "passive"))
      (node (ref "X1") (pin "C5") (pinfunction "C5_C5") (pintype "passive"))
    )
    (net (code "61") (name "I2C_SDA") (class "Default")
      (node (ref "X1") (pin "A4") (pinfunction "A4_A4") (pintype "passive"))
      (node (ref "X1") (pin "C4") (pinfunction "C4_C4") (pintype "passive"))
    )
    (net (code "62") (name "LED1") (class "Default")
      (node (ref "IC2") (pin "24") (pinfunction "PC1(ADC1)_24") (pintype "bidirectional"))
      (node (ref "R6") (pin "2") (pinfunction "2_2") (pintype "passive"))
    )
    (net (code "63") (name "LED2") (class "Default")
      (node (ref "IC2") (pin "25") (pinfunction "PC2(ADC2)_25") (pintype "bidirectional"))
      (node (ref "R7") (pin "2") (pinfunction "2_2") (pintype "passive"))
    )
    (net (code "64") (name "LED3") (class "Default")
      (node (ref "IC2") (pin "26") (pinfunction "PC3(ADC3)_26") (pintype "bidirectional"))
      (node (ref "R8") (pin "2") (pinfunction "2_2") (pintype "passive"))
    )
    (net (code "65") (name "Net-(IC1-OSC1)") (class "Default")
      (node (ref "C4") (pin "1") (pinfunction "1_1") (pintype "passive"))
      (node (ref "IC1") (pin "8") (pinfunction "OSC1_8") (pintype "input"))
      (node (ref "Q1") (pin "2") (pinfunction "2_2") (pintype "passive"))
    )
    (net (code "66") (name "Net-(IC1-OSC2)") (class "Default")
      (node (ref "C5") (pin "1") (pinfunction "1_1") (pintype "passive"))
      (node (ref "IC1") (pin "7") (pinfunction "OSC2_7") (pintype "output"))
      (node (ref "Q1") (pin "1") (pinfunction "1_1") (pintype "passive"))
    )
    (net (code "67") (name "Net-(IC1-RESET)") (class "Default")
      (node (ref "IC1") (pin "17") (pinfunction "RESET_17") (pintype "input"))
      (node (ref "R9") (pin "1") (pinfunction "1_1") (pintype "passive"))
    )
    (net (code "68") (name "Net-(IC2-PB6(XTAL1{slash}TOSC1))") (class "Default")
      (node (ref "C13") (pin "2") (pinfunction "2_2") (pintype "passive"))
      (node (ref "IC2") (pin "7") (pinfunction "PB6(XTAL1/TOSC1)_7") (pintype "bidirectional"))
      (node (ref "Q3") (pin "2") (pinfunction "2_2") (pintype "passive"))
    )
    (net (code "69") (name "Net-(IC2-PB7(XTAL2{slash}TOSC2))") (class "Default")
      (node (ref "C14") (pin "2") (pinfunction "2_2") (pintype "passive"))
      (node (ref "IC2") (pin "8") (pinfunction "PB7(XTAL2/TOSC2)_8") (pintype "bidirectional"))
      (node (ref "Q3") (pin "1") (pinfunction "1_1") (pintype "passive"))
    )
    (net (code "70") (name "Net-(IC2-PC0(ADC0))") (class "Default")
      (node (ref "IC2") (pin "23") (pinfunction "PC0(ADC0)_23") (pintype "bidirectional"))
      (node (ref "PI-RESET") (pin "1") (pinfunction "1_1") (pintype "passive"))
    )
    (net (code "71") (name "Net-(IC3-OSC1)") (class "Default")
      (node (ref "C7") (pin "1") (pinfunction "1_1") (pintype "passive"))
      (node (ref "IC3") (pin "8") (pinfunction "OSC1_8") (pintype "input"))
      (node (ref "Q2") (pin "2") (pinfunction "2_2") (pintype "passive"))
    )
    (net (code "72") (name "Net-(IC3-OSC2)") (class "Default")
      (node (ref "C8") (pin "1") (pinfunction "1_1") (pintype "passive"))
      (node (ref "IC3") (pin "7") (pinfunction "OSC2_7") (pintype "output"))
      (node (ref "Q2") (pin "1") (pinfunction "1_1") (pintype "passive"))
    )
    (net (code "73") (name "Net-(IC3-RESET)") (class "Default")
      (node (ref "IC3") (pin "17") (pinfunction "RESET_17") (pintype "input"))
      (node (ref "R10") (pin "1") (pinfunction "1_1") (pintype "passive"))
    )
    (net (code "74") (name "Net-(JP1-Pad1)") (class "Default")
      (node (ref "JP1") (pin "1") (pinfunction "1_1") (pintype "passive"))
      (node (ref "R1") (pin "2") (pinfunction "2_2") (pintype "passive"))
    )
    (net (code "75") (name "Net-(JP2-Pad1)") (class "Default")
      (node (ref "JP2") (pin "1") (pinfunction "1_1") (pintype "passive"))
      (node (ref "R2") (pin "2") (pinfunction "2_2") (pintype "passive"))
    )
    (net (code "76") (name "Net-(JP3-Pad1)") (class "Default")
      (node (ref "JP3") (pin "1") (pinfunction "1_1") (pintype "passive"))
      (node (ref "R3") (pin "2") (pinfunction "2_2") (pintype "passive"))
    )
    (net (code "77") (name "Net-(LED1-PadA)") (class "Default")
      (node (ref "LED1") (pin "A") (pinfunction "A_A") (pintype "passive"))
      (node (ref "R6") (pin "1") (pinfunction "1_1") (pintype "passive"))
    )
    (net (code "78") (name "Net-(LED2-PadA)") (class "Default")
      (node (ref "LED2") (pin "A") (pinfunction "A_A") (pintype "passive"))
      (node (ref "R7") (pin "1") (pinfunction "1_1") (pintype "passive"))
    )
    (net (code "79") (name "Net-(LED3-PadA)") (class "Default")
      (node (ref "LED3") (pin "A") (pinfunction "A_A") (pintype "passive"))
      (node (ref "R8") (pin "1") (pinfunction "1_1") (pintype "passive"))
    )
    (net (code "80") (name "PROG_DTR") (class "Default")
      (node (ref "AT-PROG") (pin "1") (pinfunction "1_1") (pintype "passive"))
      (node (ref "C11") (pin "1") (pinfunction "1_1") (pintype "passive"))
    )
    (net (code "81") (name "PROG_RX") (class "Default")
      (node (ref "AT-PROG") (pin "2") (pinfunction "2_2") (pintype "passive"))
      (node (ref "IC2") (pin "31") (pinfunction "PD1(TXD)_31") (pintype "bidirectional"))
    )
    (net (code "82") (name "PROG_TX") (class "Default")
      (node (ref "AT-PROG") (pin "3") (pinfunction "3_3") (pintype "passive"))
      (node (ref "IC2") (pin "30") (pinfunction "PD0(RXD)_30") (pintype "bidirectional"))
    )
    (net (code "83") (name "RXCAN") (class "Default")
      (node (ref "IC1") (pin "2") (pinfunction "RXCAN_2") (pintype "input"))
      (node (ref "U1") (pin "4") (pinfunction "RXD_4") (pintype "output"))
    )
    (net (code "84") (name "RXD") (class "Default")
      (node (ref "X1") (pin "C12") (pinfunction "C12_C12") (pintype "passive"))
    )
    (net (code "85") (name "SPI_CE0") (class "Default")
      (node (ref "IC1") (pin "16") (pinfunction "CS_16") (pintype "input"))
      (node (ref "X1") (pin "A10") (pinfunction "A10_A10") (pintype "passive"))
    )
    (net (code "86") (name "SPI_CE1") (class "Default")
      (node (ref "X1") (pin "C11") (pinfunction "C11_C11") (pintype "passive"))
    )
    (net (code "87") (name "SPI_MISO") (class "Default")
      (node (ref "IC1") (pin "15") (pinfunction "SO_15") (pintype "output"))
      (node (ref "X1") (pin "A9") (pinfunction "A9_A9") (pintype "passive"))
    )
    (net (code "88") (name "SPI_MOSI") (class "Default")
      (node (ref "IC1") (pin "14") (pinfunction "SI_14") (pintype "input"))
      (node (ref "X1") (pin "C9") (pinfunction "C9_C9") (pintype "passive"))
    )
    (net (code "89") (name "SPI_SCLK") (class "Default")
      (node (ref "IC1") (pin "13") (pinfunction "SCK_13") (pintype "input"))
      (node (ref "X1") (pin "C10") (pinfunction "C10_C10") (pintype "passive"))
    )
    (net (code "90") (name "TXCAN") (class "Default")
      (node (ref "IC1") (pin "1") (pinfunction "TXCAN_1") (pintype "output"))
      (node (ref "U1") (pin "1") (pinfunction "TXD_1") (pintype "input"))
    )
    (net (code "91") (name "TXD") (class "Default")
      (node (ref "X1") (pin "A12") (pinfunction "A12_A12") (pintype "passive"))
    )
    (net (code "92") (name "unconnected-(AT-PROG-Pad4)") (class "Default")
      (node (ref "AT-PROG") (pin "4") (pinfunction "4_4") (pintype "passive"))
    )
    (net (code "93") (name "unconnected-(AT-PROG-Pad5)") (class "Default")
      (node (ref "AT-PROG") (pin "5") (pinfunction "5_5") (pintype "passive"))
    )
    (net (code "94") (name "unconnected-(IC1-CLKOUT-Pad3)") (class "Default")
      (node (ref "IC1") (pin "3") (pinfunction "CLKOUT_3") (pintype "output"))
    )
    (net (code "95") (name "unconnected-(IC1-RX0BF-Pad11)") (class "Default")
      (node (ref "IC1") (pin "11") (pinfunction "RX0BF_11") (pintype "output"))
    )
    (net (code "96") (name "unconnected-(IC1-RX1BF-Pad10)") (class "Default")
      (node (ref "IC1") (pin "10") (pinfunction "RX1BF_10") (pintype "output"))
    )
    (net (code "97") (name "unconnected-(IC1-TX0RTS-Pad4)") (class "Default")
      (node (ref "IC1") (pin "4") (pinfunction "TX0RTS_4") (pintype "input"))
    )
    (net (code "98") (name "unconnected-(IC1-TX1RTS-Pad5)") (class "Default")
      (node (ref "IC1") (pin "5") (pinfunction "TX1RTS_5") (pintype "input"))
    )
    (net (code "99") (name "unconnected-(IC1-TX2RTS-Pad6)") (class "Default")
      (node (ref "IC1") (pin "6") (pinfunction "TX2RTS_6") (pintype "input"))
    )
    (net (code "100") (name "unconnected-(IC2-ADC6-Pad19)") (class "Default")
      (node (ref "IC2") (pin "19") (pinfunction "ADC6_19") (pintype "bidirectional"))
    )
    (net (code "101") (name "unconnected-(IC2-ADC7-Pad22)") (class "Default")
      (node (ref "IC2") (pin "22") (pinfunction "ADC7_22") (pintype "bidirectional"))
    )
    (net (code "102") (name "unconnected-(IC2-AREF-Pad20)") (class "Default")
      (node (ref "IC2") (pin "20") (pinfunction "AREF_20") (pintype "passive"))
    )
    (net (code "103") (name "unconnected-(IC3-CLKOUT-Pad3)") (class "Default")
      (node (ref "IC3") (pin "3") (pinfunction "CLKOUT_3") (pintype "output"))
    )
    (net (code "104") (name "unconnected-(IC3-RX0BF-Pad11)") (class "Default")
      (node (ref "IC3") (pin "11") (pinfunction "RX0BF_11") (pintype "output"))
    )
    (net (code "105") (name "unconnected-(IC3-RX1BF-Pad10)") (class "Default")
      (node (ref "IC3") (pin "10") (pinfunction "RX1BF_10") (pintype "output"))
    )
    (net (code "106") (name "unconnected-(IC3-TX0RTS-Pad4)") (class "Default")
      (node (ref "IC3") (pin "4") (pinfunction "TX0RTS_4") (pintype "input"))
    )
    (net (code "107") (name "unconnected-(IC3-TX1RTS-Pad5)") (class "Default")
      (node (ref "IC3") (pin "5") (pinfunction "TX1RTS_5") (pintype "input"))
    )
    (net (code "108") (name "unconnected-(IC3-TX2RTS-Pad6)") (class "Default")
      (node (ref "IC3") (pin "6") (pinfunction "TX2RTS_6") (pintype "input"))
    )
    (net (code "109") (name "~{AT_RESET}") (class "Default")
      (node (ref "AT-ISP") (pin "5") (pinfunction "5_5") (pintype "passive"))
      (node (ref "AT-RESET") (pin "3") (pinfunction "S_3") (pintype "passive"))
      (node (ref "AT-RESET") (pin "4") (pinfunction "S1_4") (pintype "passive"))
      (node (ref "C11") (pin "2") (pinfunction "2_2") (pintype "passive"))
      (node (ref "IC2") (pin "29") (pinfunction "PC6(/RESET)_29") (pintype "bidirectional"))
      (node (ref "R5") (pin "1") (pinfunction "1_1") (pintype "passive"))
    )
    (net (code "110") (name "~{PI_RESET}") (class "Default")
      (node (ref "PI-RESET") (pin "2") (pinfunction "2_2") (pintype "passive"))
      (node (ref "X1") (pin "A26") (pinfunction "A26_A26") (pintype "passive"))
    )
  )
)
